# ProPrj_usb__2025-12-08-14-59-02.net
KiCad netlist of a schematic drawn in EasyEDA Pro
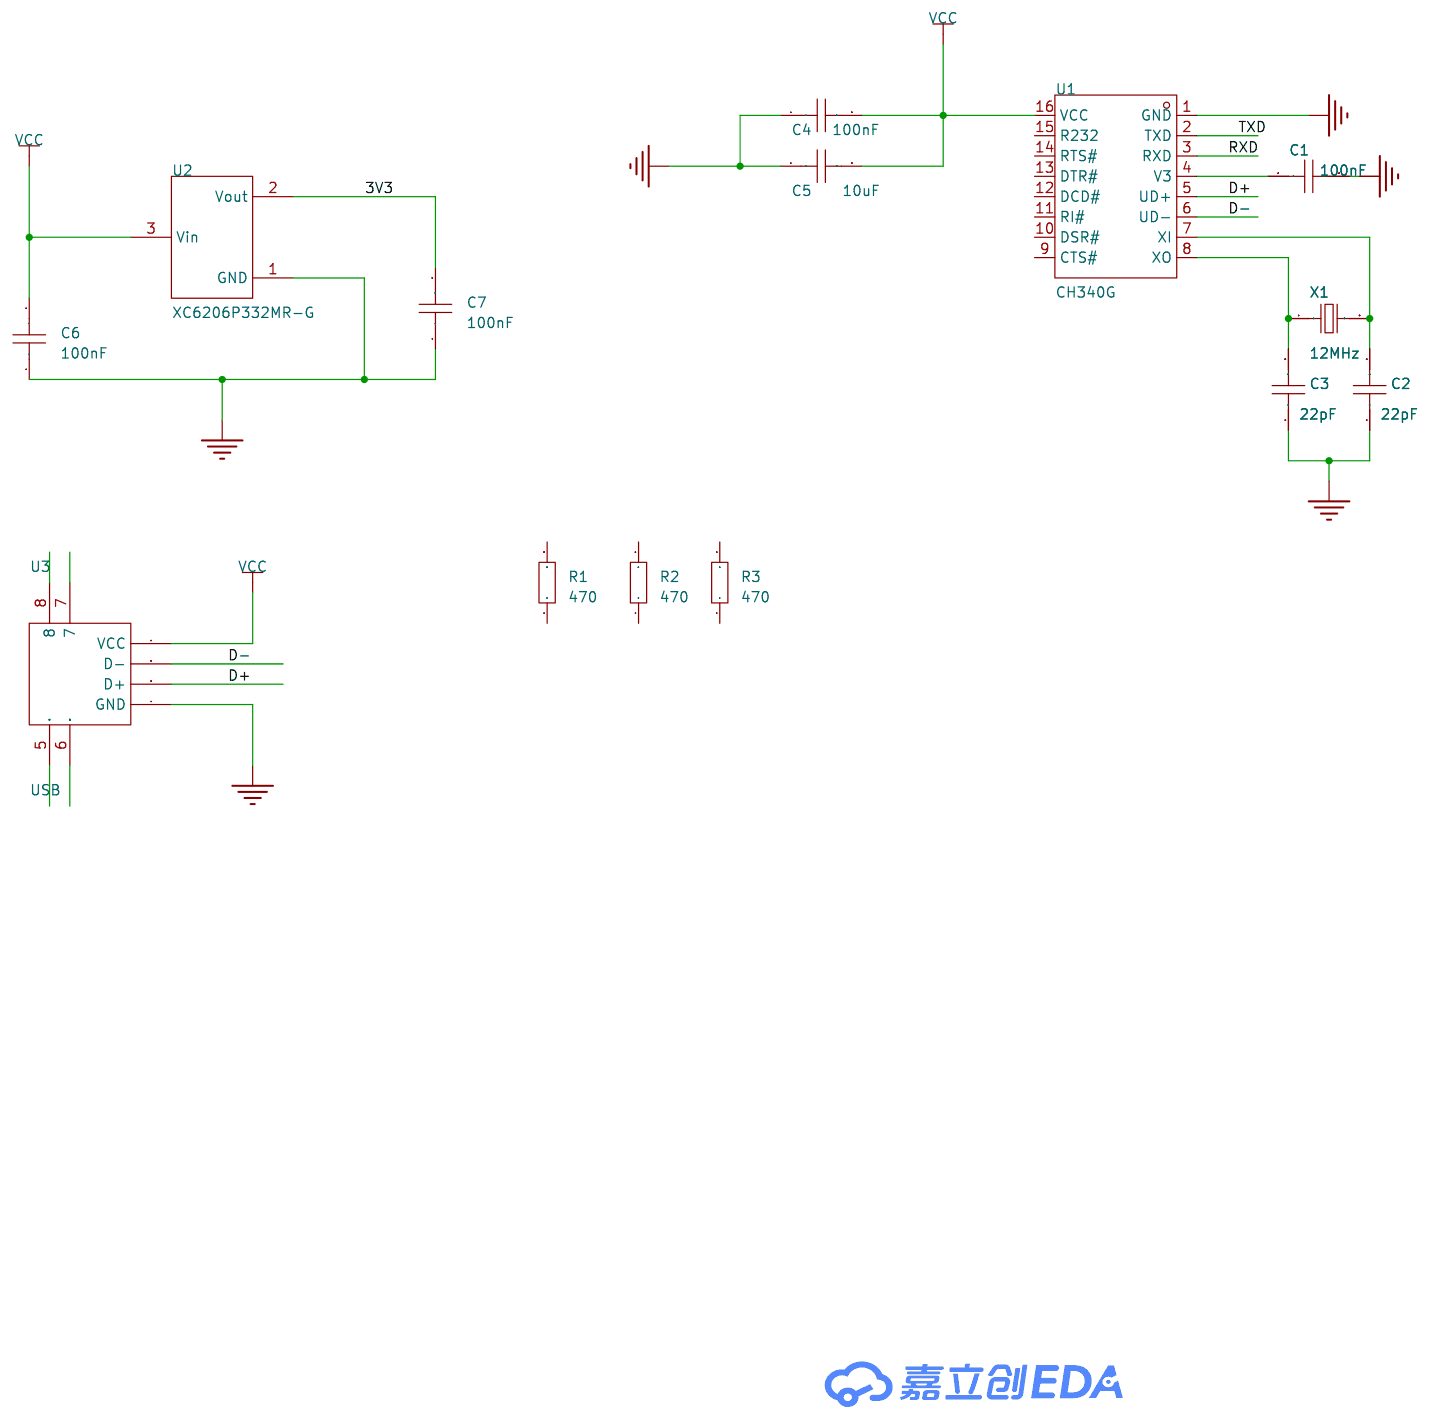
[diagram p0: schematic sheet]

(export (version "E")
  (design (tool "Eeschema 10.0.6"))
  (components
    (comp (ref "C1")
      (value "100nF")
      (footprint "easyedapro:C0603")
      (libsource (lib "easyedapro") (part "Capacitance"))
    )
    (comp (ref "C2")
      (value "22pF")
      (footprint "easyedapro:C0603")
      (libsource (lib "easyedapro") (part "Capacitance"))
    )
    (comp (ref "C3")
      (value "22pF")
      (footprint "easyedapro:C0603")
      (libsource (lib "easyedapro") (part "Capacitance"))
    )
    (comp (ref "C4")
      (value "100nF")
      (footprint "easyedapro:C0603")
      (libsource (lib "easyedapro") (part "Capacitance"))
    )
    (comp (ref "C5")
      (value "10uF")
      (footprint "easyedapro:C0603")
      (libsource (lib "easyedapro") (part "Capacitance"))
    )
    (comp (ref "C6")
      (value "100nF")
      (footprint "easyedapro:C0603")
      (libsource (lib "easyedapro") (part "Capacitance"))
    )
    (comp (ref "C7")
      (value "100nF")
      (footprint "easyedapro:C0603")
      (libsource (lib "easyedapro") (part "Capacitance"))
    )
    (comp (ref "R1") (value "470") (footprint "easyedapro:R0603") (libsource (lib "easyedapro") (part "电阻")))
    (comp (ref "R2") (value "470") (footprint "easyedapro:R0603") (libsource (lib "easyedapro") (part "电阻")))
    (comp (ref "R3") (value "470") (footprint "easyedapro:R0603") (libsource (lib "easyedapro") (part "电阻")))
    (comp (ref "U1")
      (value "CH340G")
      (footprint "easyedapro:SOIC-16_L9.9-W3.9-P1.27-LS6.0-BL")
      (description "应用功能:USB转UART;接口协议:USB 2.0;数据速率:2Mbps;")
      (fields (field (name "Manufacturer") "WCH(南京沁恒)"))
      (libsource (lib "easyedapro") (part "CH340G"))
    )
    (comp (ref "U2")
      (value "XC6206P332MR-G")
      (footprint "easyedapro:SOT-23-3_L2.9-W1.6-P1.90-LS2.8-BR")
      (description "输出类型:固定;工作电压:6V;输出电压:3.3V;输出电流:200mA;电源纹波抑制比(PSRR):-;输出极性:正极;")
      (fields (field (name "Manufacturer") "TOREX(特瑞仕)"))
      (libsource (lib "easyedapro") (part "XC6206P332MR"))
    )
    (comp (ref "U3")
      (value "USB")
      (footprint "easyedapro:USB-SMD_USB_1")
      (libsource (lib "easyedapro") (part "USB"))
    )
    (comp (ref "X1")
      (value "12MHz")
      (footprint "easyedapro:CRYSTAL-SMD_L5.0-W3.2")
      (description "晶振类型:贴片晶振;频率:12MHz;常温频差:±20ppm;负载电容:20pF;频率稳定度:±30ppm;")
      (fields
        (field (name "Manufacturer Part") "XC53G2-12.000-F20LJDT")
        (field (name "Manufacturer") "HCI(杭晶)")
      )
      (libsource (lib "easyedapro") (part "XC53G2-12.000-F20LJDT"))
    )
  )
  (nets
    (net (code "1") (name "/3V3") (class "Default")
      (node (ref "C7") (pin "2") (pinfunction "2_2") (pintype "input"))
      (node (ref "U2") (pin "2") (pinfunction "Vout_2") (pintype "unspecified"))
    )
    (net (code "2") (name "/D+") (class "Default")
      (node (ref "U1") (pin "5") (pinfunction "UD+_5") (pintype "unspecified"))
      (node (ref "U3") (pin "3") (pinfunction "D+_3") (pintype "input"))
    )
    (net (code "3") (name "/D-") (class "Default")
      (node (ref "U1") (pin "6") (pinfunction "UD-_6") (pintype "unspecified"))
      (node (ref "U3") (pin "2") (pinfunction "D-_2") (pintype "input"))
    )
    (net (code "4") (name "/RXD") (class "Default")
      (node (ref "U1") (pin "3") (pinfunction "RXD_3") (pintype "unspecified"))
    )
    (net (code "5") (name "/TXD") (class "Default")
      (node (ref "U1") (pin "2") (pinfunction "TXD_2") (pintype "unspecified"))
    )
    (net (code "6") (name "GND") (class "Default")
      (node (ref "C1") (pin "2") (pinfunction "2_2") (pintype "input"))
      (node (ref "C2") (pin "1") (pinfunction "1_1") (pintype "input"))
      (node (ref "C3") (pin "1") (pinfunction "1_1") (pintype "input"))
      (node (ref "C4") (pin "1") (pinfunction "1_1") (pintype "input"))
      (node (ref "C5") (pin "1") (pinfunction "1_1") (pintype "input"))
      (node (ref "C6") (pin "1") (pinfunction "1_1") (pintype "input"))
      (node (ref "C7") (pin "1") (pinfunction "1_1") (pintype "input"))
      (node (ref "U1") (pin "1") (pinfunction "GND_1") (pintype "unspecified"))
      (node (ref "U2") (pin "1") (pinfunction "GND_1") (pintype "unspecified"))
      (node (ref "U3") (pin "4") (pinfunction "GND_4") (pintype "input"))
    )
    (net (code "7") (name "Net-(U1-V3)") (class "Default")
      (node (ref "C1") (pin "1") (pinfunction "1_1") (pintype "input"))
      (node (ref "U1") (pin "4") (pinfunction "V3_4") (pintype "unspecified"))
    )
    (net (code "8") (name "Net-(U1-XI)") (class "Default")
      (node (ref "C2") (pin "2") (pinfunction "2_2") (pintype "input"))
      (node (ref "U1") (pin "7") (pinfunction "XI_7") (pintype "unspecified"))
      (node (ref "X1") (pin "2") (pinfunction "2_2") (pintype "unspecified"))
    )
    (net (code "9") (name "Net-(U1-XO)") (class "Default")
      (node (ref "C3") (pin "2") (pinfunction "2_2") (pintype "input"))
      (node (ref "U1") (pin "8") (pinfunction "XO_8") (pintype "unspecified"))
      (node (ref "X1") (pin "1") (pinfunction "1_1") (pintype "unspecified"))
    )
    (net (code "10") (name "VCC") (class "Default")
      (node (ref "C4") (pin "2") (pinfunction "2_2") (pintype "input"))
      (node (ref "C5") (pin "2") (pinfunction "2_2") (pintype "input"))
      (node (ref "C6") (pin "2") (pinfunction "2_2") (pintype "input"))
      (node (ref "U1") (pin "16") (pinfunction "VCC_16") (pintype "unspecified"))
      (node (ref "U2") (pin "3") (pinfunction "Vin_3") (pintype "unspecified"))
      (node (ref "U3") (pin "1") (pinfunction "VCC_1") (pintype "input"))
    )
    (net (code "11") (name "unconnected-(R1-Pad1)") (class "Default")
      (node (ref "R1") (pin "1") (pinfunction "1_1") (pintype "input"))
    )
    (net (code "12") (name "unconnected-(R1-Pad2)") (class "Default")
      (node (ref "R1") (pin "2") (pinfunction "2_2") (pintype "input"))
    )
    (net (code "13") (name "unconnected-(R2-Pad1)") (class "Default")
      (node (ref "R2") (pin "1") (pinfunction "1_1") (pintype "input"))
    )
    (net (code "14") (name "unconnected-(R2-Pad2)") (class "Default")
      (node (ref "R2") (pin "2") (pinfunction "2_2") (pintype "input"))
    )
    (net (code "15") (name "unconnected-(R3-Pad1)") (class "Default")
      (node (ref "R3") (pin "1") (pinfunction "1_1") (pintype "input"))
    )
    (net (code "16") (name "unconnected-(R3-Pad2)") (class "Default")
      (node (ref "R3") (pin "2") (pinfunction "2_2") (pintype "input"))
    )
    (net (code "17") (name "unconnected-(U1-CTS#-Pad9)") (class "Default")
      (node (ref "U1") (pin "9") (pinfunction "CTS#_9") (pintype "unspecified"))
    )
    (net (code "18") (name "unconnected-(U1-DCD#-Pad12)") (class "Default")
      (node (ref "U1") (pin "12") (pinfunction "DCD#_12") (pintype "unspecified"))
    )
    (net (code "19") (name "unconnected-(U1-DSR#-Pad10)") (class "Default")
      (node (ref "U1") (pin "10") (pinfunction "DSR#_10") (pintype "unspecified"))
    )
    (net (code "20") (name "unconnected-(U1-DTR#-Pad13)") (class "Default")
      (node (ref "U1") (pin "13") (pinfunction "DTR#_13") (pintype "unspecified"))
    )
    (net (code "21") (name "unconnected-(U1-R232-Pad15)") (class "Default")
      (node (ref "U1") (pin "15") (pinfunction "R232_15") (pintype "unspecified"))
    )
    (net (code "22") (name "unconnected-(U1-RI#-Pad11)") (class "Default")
      (node (ref "U1") (pin "11") (pinfunction "RI#_11") (pintype "unspecified"))
    )
    (net (code "23") (name "unconnected-(U1-RTS#-Pad14)") (class "Default")
      (node (ref "U1") (pin "14") (pinfunction "RTS#_14") (pintype "unspecified"))
    )
    (net (code "24") (name "unconnected-(U3-Pad7)") (class "Default")
      (node (ref "U3") (pin "7") (pinfunction "7_7") (pintype "unspecified"))
    )
    (net (code "25") (name "unconnected-(U3-Pad8)") (class "Default")
      (node (ref "U3") (pin "8") (pinfunction "8_8") (pintype "unspecified"))
    )
    (net (code "26") (name "unconnected-(U3-SH1-Pad5)") (class "Default")
      (node (ref "U3") (pin "5") (pinfunction "SH1_5") (pintype "unspecified"))
    )
    (net (code "27") (name "unconnected-(U3-SH2-Pad6)") (class "Default")
      (node (ref "U3") (pin "6") (pinfunction "SH2_6") (pintype "unspecified"))
    )
  )
)
